# 2025_07_18_imu.net
KiCad netlist of a schematic drawn in EasyEDA Pro
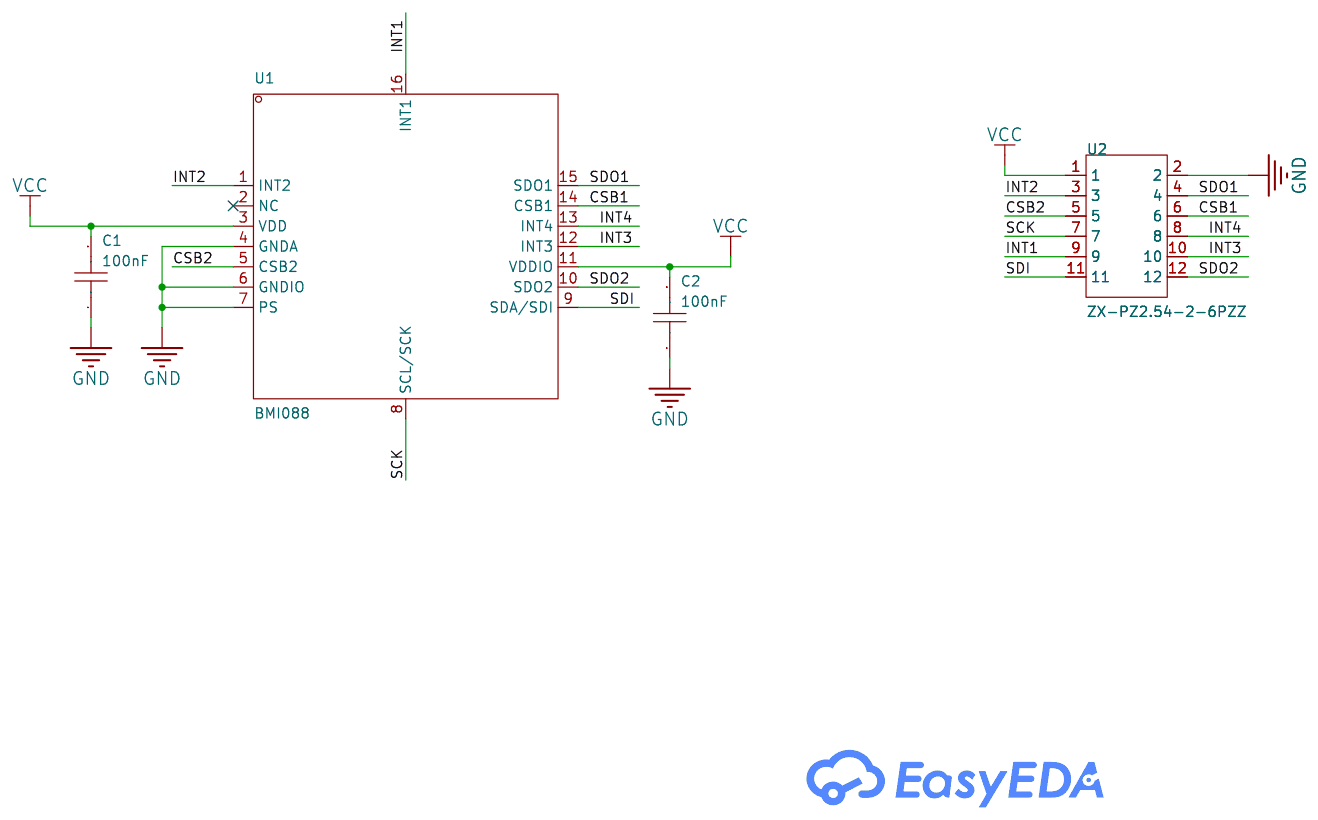
[diagram p0: schematic sheet]

(export (version "E")
  (design (tool "Eeschema 10.0.6"))
  (components
    (comp (ref "C1")
      (value "100nF")
      (footprint "easyedapro:C0402")
      (fields
        (field (name "Manufacturer Part") "CL05B104KO5NNNC")
        (field (name "Manufacturer") "SAMSUNG(三星)")
      )
      (libsource (lib "easyedapro") (part "CL05B104KO5NNNC"))
    )
    (comp (ref "C2")
      (value "100nF")
      (footprint "easyedapro:C0402")
      (fields
        (field (name "Manufacturer Part") "CL05B104KO5NNNC")
        (field (name "Manufacturer") "SAMSUNG(三星)")
      )
      (libsource (lib "easyedapro") (part "CL05B104KO5NNNC"))
    )
    (comp (ref "U1")
      (value "BMI088")
      (footprint "easyedapro:LGA-16_L4.5-W3.0-P0.50-BL")
      (description "Sensor Type:加速度计陀螺仪 Operating Temperature:-40°C~+85°C Operating Temperature:-40°C~+85°C")
      (fields (field (name "Manufacturer") "Bosch(博世)"))
      (libsource (lib "easyedapro") (part "BMI088"))
    )
    (comp (ref "U2")
      (value "ZX-PZ2.54-2-6PZZ")
      (footprint "easyedapro:HDR-TH_12P-P2.54-V-M-R2-C6-S2.54")
      (fields (field (name "Manufacturer") "Megastar(兆星)"))
      (libsource (lib "easyedapro") (part "ZX-PZ2.54-2-6PZZ"))
    )
  )
  (nets
    (net (code "1") (name "/CSB1") (class "Default")
      (node (ref "U1") (pin "14") (pinfunction "CSB1_14") (pintype "input"))
      (node (ref "U2") (pin "6") (pinfunction "6_6") (pintype "unspecified"))
    )
    (net (code "2") (name "/CSB2") (class "Default")
      (node (ref "U1") (pin "5") (pinfunction "CSB2_5") (pintype "input"))
      (node (ref "U2") (pin "5") (pinfunction "5_5") (pintype "unspecified"))
    )
    (net (code "3") (name "/INT1") (class "Default")
      (node (ref "U1") (pin "16") (pinfunction "INT1_16") (pintype "input"))
      (node (ref "U2") (pin "9") (pinfunction "9_9") (pintype "unspecified"))
    )
    (net (code "4") (name "/INT2") (class "Default")
      (node (ref "U1") (pin "1") (pinfunction "INT2_1") (pintype "input"))
      (node (ref "U2") (pin "3") (pinfunction "3_3") (pintype "unspecified"))
    )
    (net (code "5") (name "/INT3") (class "Default")
      (node (ref "U1") (pin "12") (pinfunction "INT3_12") (pintype "input"))
      (node (ref "U2") (pin "10") (pinfunction "10_10") (pintype "unspecified"))
    )
    (net (code "6") (name "/INT4") (class "Default")
      (node (ref "U1") (pin "13") (pinfunction "INT4_13") (pintype "input"))
      (node (ref "U2") (pin "8") (pinfunction "8_8") (pintype "unspecified"))
    )
    (net (code "7") (name "/SCK") (class "Default")
      (node (ref "U1") (pin "8") (pinfunction "SCL/SCK_8") (pintype "input"))
      (node (ref "U2") (pin "7") (pinfunction "7_7") (pintype "unspecified"))
    )
    (net (code "8") (name "/SDI") (class "Default")
      (node (ref "U1") (pin "9") (pinfunction "SDA/SDI_9") (pintype "input"))
      (node (ref "U2") (pin "11") (pinfunction "11_11") (pintype "unspecified"))
    )
    (net (code "9") (name "/SDO1") (class "Default")
      (node (ref "U1") (pin "15") (pinfunction "SDO1_15") (pintype "input"))
      (node (ref "U2") (pin "4") (pinfunction "4_4") (pintype "unspecified"))
    )
    (net (code "10") (name "/SDO2") (class "Default")
      (node (ref "U1") (pin "10") (pinfunction "SDO2_10") (pintype "input"))
      (node (ref "U2") (pin "12") (pinfunction "12_12") (pintype "unspecified"))
    )
    (net (code "11") (name "GND") (class "Default")
      (node (ref "C1") (pin "1") (pinfunction "1_1") (pintype "unspecified"))
      (node (ref "C2") (pin "1") (pinfunction "1_1") (pintype "unspecified"))
      (node (ref "U1") (pin "4") (pinfunction "GNDA_4") (pintype "input"))
      (node (ref "U1") (pin "6") (pinfunction "GNDIO_6") (pintype "input"))
      (node (ref "U1") (pin "7") (pinfunction "PS_7") (pintype "input"))
      (node (ref "U2") (pin "2") (pinfunction "2_2") (pintype "unspecified"))
    )
    (net (code "12") (name "VCC") (class "Default")
      (node (ref "C1") (pin "2") (pinfunction "2_2") (pintype "unspecified"))
      (node (ref "C2") (pin "2") (pinfunction "2_2") (pintype "unspecified"))
      (node (ref "U1") (pin "11") (pinfunction "VDDIO_11") (pintype "input"))
      (node (ref "U1") (pin "3") (pinfunction "VDD_3") (pintype "input"))
      (node (ref "U2") (pin "1") (pinfunction "1_1") (pintype "unspecified"))
    )
    (net (code "13") (name "unconnected-(U1-NC-Pad2)") (class "Default")
      (node (ref "U1") (pin "2") (pinfunction "NC_2") (pintype "input+no_connect"))
    )
  )
)
